# 01POWER.net
KiCad netlist of a schematic drawn in Altium Designer
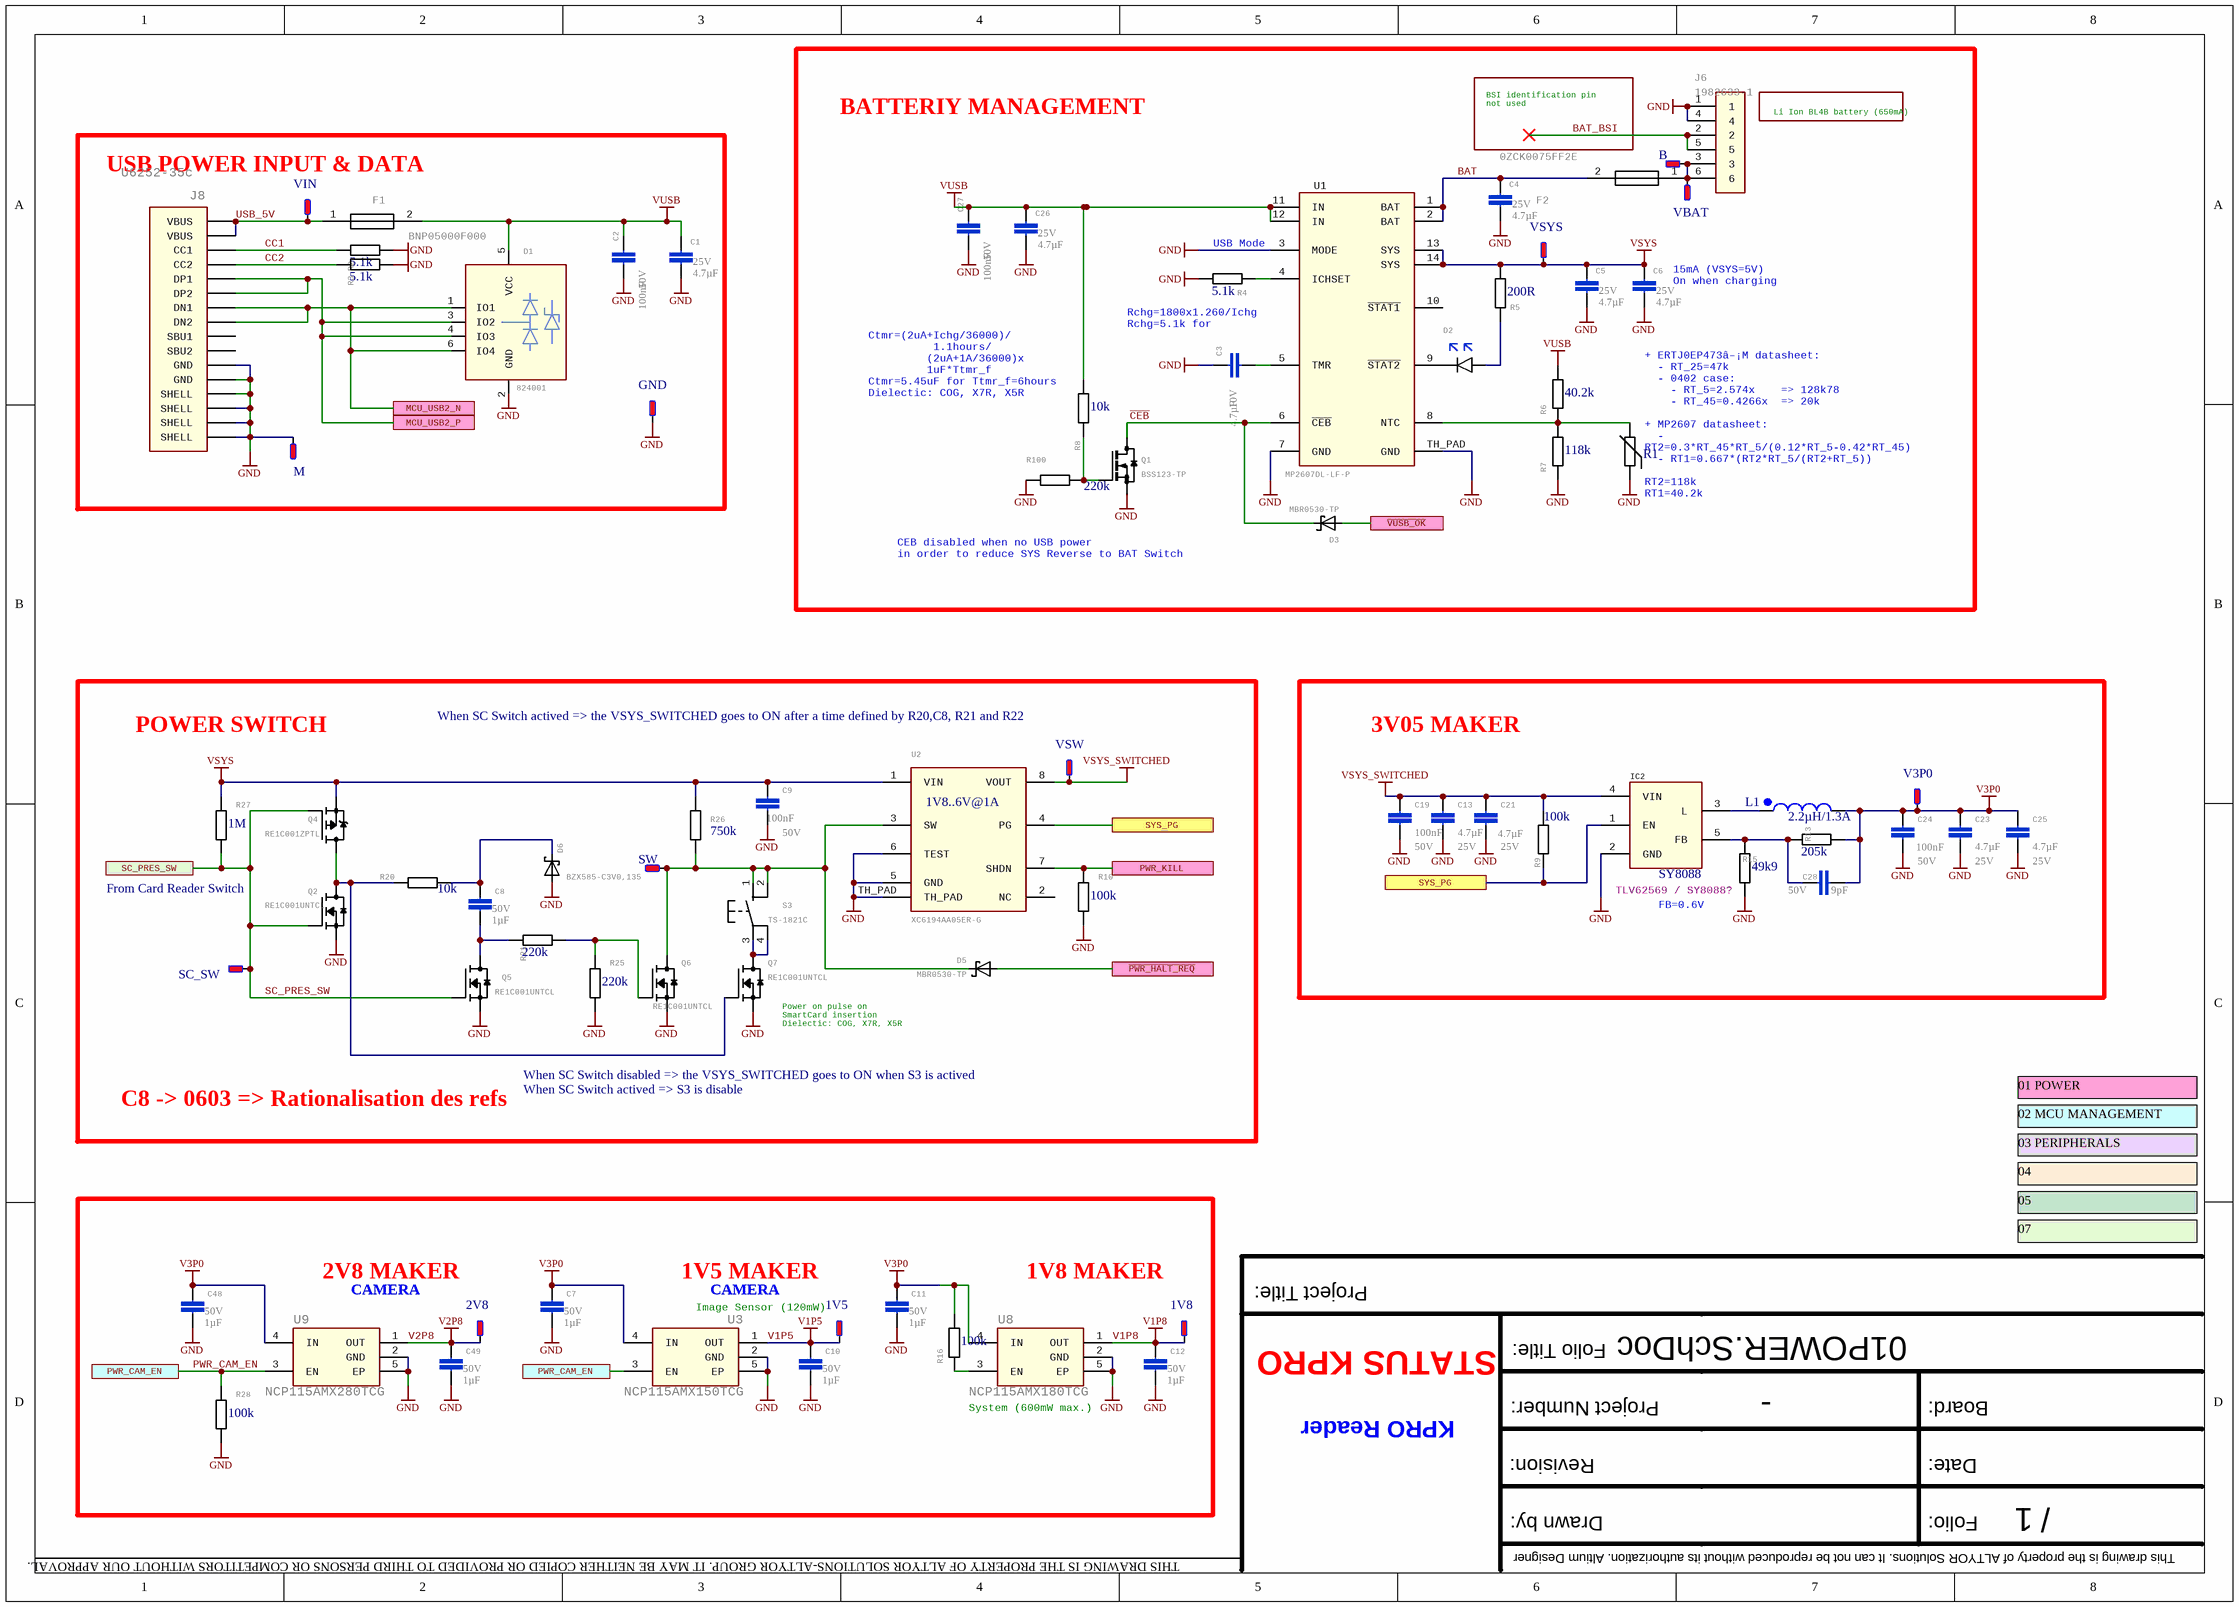
[diagram p0: 01POWER.SchDoc]

(export (version "E")
  (design (tool "Eeschema 10.0.6"))
  (components
    (comp (ref "1V5")
      (value "TP")
      (footprint "TESTPOINT 1MM")
      (description "Pointe de test 1.27mm")
      (libsource (lib "KCP-2282-600") (part "TP"))
    )
    (comp (ref "1V8")
      (value "TP")
      (footprint "TESTPOINT 1MM")
      (description "Pointe de test 1.27mm")
      (libsource (lib "KCP-2282-600") (part "TP"))
    )
    (comp (ref "2V8")
      (value "TP")
      (footprint "TESTPOINT 1MM")
      (description "Pointe de test 1.27mm")
      (libsource (lib "KCP-2282-600") (part "TP"))
    )
    (comp (ref "B")
      (value "TP")
      (footprint "PLAGE - ROUGE")
      (description "Pointe de test 1.27mm")
      (libsource (lib "KCP-2282-600") (part "TP"))
    )
    (comp (ref "C1")
      (value "0805X475M250CT")
      (footprint "0805 - CAPACITOR")
      (description "CAP X5R 4.7µF 25V ±10% 0805")
      (fields
        (field (name "MANUFACTURER") "WALSIN")
        (field (name "VOLTAGE") "25V")
        (field (name "NAME") "4.7µF")
      )
      (libsource (lib "KCP-2282-600") (part "C-EU-C4.7µF-X5R-6.3V-0805"))
    )
    (comp (ref "C2")
      (value "0402B104K500CT")
      (footprint "0402 - CAPACITOR")
      (description "CAP X7R 100nF 50V ±10% 0402")
      (fields
        (field (name "MANUFACTURER") "WALSIN")
        (field (name "VOLTAGE") "50V")
        (field (name "NAME") "100nF")
      )
      (libsource (lib "KCP-2282-600") (part "C-EU-C100NF-X7R-16V-0402"))
    )
    (comp (ref "C3")
      (value "CC0402KRX5R6BB475")
      (footprint "0402 - CAPACITOR")
      (description "CAP X5R 4.7µF 10V ±10% 0402")
      (fields
        (field (name "MANUFACTURER") "YAGEO")
        (field (name "VOLTAGE") "10V")
        (field (name "NAME") "4.7µF")
      )
      (libsource (lib "KCP-2282-600") (part "C-EU-C5UF-X7R-6.3V-0402"))
    )
    (comp (ref "C4")
      (value "0805X475M250CT")
      (footprint "0805 - CAPACITOR")
      (description "CAP X5R 4.7µF 25V ±10% 0805")
      (fields
        (field (name "MANUFACTURER") "WALSIN")
        (field (name "VOLTAGE") "25V")
        (field (name "NAME") "4.7µF")
      )
      (libsource (lib "KCP-2282-600") (part "C-EU-C4.7µF-X5R-6.3V-0805"))
    )
    (comp (ref "C5")
      (value "0805X475M250CT")
      (footprint "0805 - CAPACITOR")
      (description "CAP X5R 4.7µF 25V ±10% 0805")
      (fields
        (field (name "MANUFACTURER") "WALSIN")
        (field (name "VOLTAGE") "25V")
        (field (name "NAME") "4.7µF")
      )
      (libsource (lib "KCP-2282-600") (part "C-EU-C4.7µF-X5R-6.3V-0805"))
    )
    (comp (ref "C6")
      (value "0805X475M250CT")
      (footprint "0805 - CAPACITOR")
      (description "CAP X5R 4.7µF 25V ±10% 0805")
      (fields
        (field (name "MANUFACTURER") "WALSIN")
        (field (name "VOLTAGE") "25V")
        (field (name "NAME") "4.7µF")
      )
      (libsource (lib "KCP-2282-600") (part "C-EU-C4.7µF-X5R-6.3V-0805"))
    )
    (comp (ref "C7")
      (value "0603X105K500CT")
      (footprint "0603 - CAPACITOR")
      (description "CAP X5R 1µF 50V ±10% 0603")
      (fields
        (field (name "MANUFACTURER") "WALSIN")
        (field (name "VOLTAGE") "50V")
        (field (name "NAME") "1µF")
      )
      (libsource (lib "KCP-2282-600") (part "C-EU-C1µF-X5R-6.3V-0603"))
    )
    (comp (ref "C8")
      (value "0603X105K500CT")
      (footprint "0603 - CAPACITOR")
      (description "CAP X5R 1µF 50V ±10% 0603")
      (fields
        (field (name "MANUFACTURER") "WALSIN")
        (field (name "VOLTAGE") "50V")
        (field (name "NAME") "1µF")
      )
      (libsource (lib "KCP-2282-600") (part "C-EU-C1µF-X5R-6.3V-0603"))
    )
    (comp (ref "C9")
      (value "0402B104K500CT")
      (footprint "0402 - CAPACITOR")
      (description "CAP X7R 100nF 50V ±10% 0402")
      (fields
        (field (name "MANUFACTURER") "WALSIN")
        (field (name "VOLTAGE") "50V")
        (field (name "NAME") "100nF")
      )
      (libsource (lib "KCP-2282-600") (part "C-EU-C100NF-X7R-16V-0402"))
    )
    (comp (ref "C10")
      (value "0603X105K500CT")
      (footprint "0603 - CAPACITOR")
      (description "CAP X5R 1µF 50V ±10% 0603")
      (fields
        (field (name "MANUFACTURER") "WALSIN")
        (field (name "VOLTAGE") "50V")
        (field (name "NAME") "1µF")
      )
      (libsource (lib "KCP-2282-600") (part "C-EU-C1µF-X5R-6.3V-0603"))
    )
    (comp (ref "C11")
      (value "0603X105K500CT")
      (footprint "0603 - CAPACITOR")
      (description "CAP X5R 1µF 50V ±10% 0603")
      (fields
        (field (name "MANUFACTURER") "WALSIN")
        (field (name "VOLTAGE") "50V")
        (field (name "NAME") "1µF")
      )
      (libsource (lib "KCP-2282-600") (part "C-EU-C1µF-X5R-6.3V-0603"))
    )
    (comp (ref "C12")
      (value "0603X105K500CT")
      (footprint "0603 - CAPACITOR")
      (description "CAP X5R 1µF 50V ±10% 0603")
      (fields
        (field (name "MANUFACTURER") "WALSIN")
        (field (name "VOLTAGE") "50V")
        (field (name "NAME") "1µF")
      )
      (libsource (lib "KCP-2282-600") (part "C-EU-C1µF-X5R-6.3V-0603"))
    )
    (comp (ref "C13")
      (value "0805X475M250CT")
      (footprint "0805 - CAPACITOR")
      (description "CAP X5R 4.7µF 25V ±10% 0805")
      (fields
        (field (name "MANUFACTURER") "WALSIN")
        (field (name "VOLTAGE") "25V")
        (field (name "NAME") "4.7µF")
      )
      (libsource (lib "KCP-2282-600") (part "C-EU-C4.7µF-X5R-6.3V-0805"))
    )
    (comp (ref "C19")
      (value "0402B104K500CT")
      (footprint "0402 - CAPACITOR")
      (description "CAP X7R 100nF 50V ±10% 0402")
      (fields
        (field (name "MANUFACTURER") "WALSIN")
        (field (name "VOLTAGE") "50V")
        (field (name "NAME") "100nF")
      )
      (libsource (lib "KCP-2282-600") (part "C-EU-C100NF-X7R-16V-0402"))
    )
    (comp (ref "C21")
      (value "0805X475M250CT")
      (footprint "0805 - CAPACITOR")
      (description "CAP X5R 4.7µF 25V ±10% 0805")
      (fields
        (field (name "MANUFACTURER") "WALSIN")
        (field (name "VOLTAGE") "25V")
        (field (name "NAME") "4.7µF")
      )
      (libsource (lib "KCP-2282-600") (part "C-EU-C4.7µF-X5R-6.3V-0805"))
    )
    (comp (ref "C23")
      (value "0805X475M250CT")
      (footprint "0805 - CAPACITOR")
      (description "CAP X5R 4.7µF 25V ±10% 0805")
      (fields
        (field (name "MANUFACTURER") "WALSIN")
        (field (name "VOLTAGE") "25V")
        (field (name "NAME") "4.7µF")
      )
      (libsource (lib "KCP-2282-600") (part "C-EU-C4.7µF-X5R-6.3V-0805"))
    )
    (comp (ref "C24")
      (value "0402B104K500CT")
      (footprint "0402 - CAPACITOR")
      (description "CAP X7R 100nF 50V ±10% 0402")
      (fields
        (field (name "MANUFACTURER") "WALSIN")
        (field (name "VOLTAGE") "50V")
        (field (name "NAME") "100nF")
      )
      (libsource (lib "KCP-2282-600") (part "C-EU-C100NF-X7R-16V-0402"))
    )
    (comp (ref "C25")
      (value "0805X475M250CT")
      (footprint "0805 - CAPACITOR")
      (description "CAP X5R 4.7µF 25V ±10% 0805")
      (fields
        (field (name "MANUFACTURER") "WALSIN")
        (field (name "VOLTAGE") "25V")
        (field (name "NAME") "4.7µF")
      )
      (libsource (lib "KCP-2282-600") (part "C-EU-C4.7µF-X5R-6.3V-0805"))
    )
    (comp (ref "C26")
      (value "0805X475M250CT")
      (footprint "0805 - CAPACITOR")
      (description "CAP X5R 4.7µF 25V ±10% 0805")
      (fields
        (field (name "MANUFACTURER") "WALSIN")
        (field (name "VOLTAGE") "25V")
        (field (name "NAME") "4.7µF")
      )
      (libsource (lib "KCP-2282-600") (part "C-EU-C4.7µF-X5R-6.3V-0805"))
    )
    (comp (ref "C27")
      (value "0402B104K500CT")
      (footprint "0402 - CAPACITOR")
      (description "CAP X7R 100nF 50V ±10% 0402")
      (fields
        (field (name "MANUFACTURER") "WALSIN")
        (field (name "VOLTAGE") "50V")
        (field (name "NAME") "100nF")
      )
      (libsource (lib "KCP-2282-600") (part "C-EU-C100NF-X7R-16V-0402"))
    )
    (comp (ref "C28")
      (value "0402N9R0B500CT")
      (footprint "0402 - CAPACITOR")
      (description "CAP COG 9pF 50V ±0.1pF 0402")
      (fields
        (field (name "MANUFACTURER") "WALSIN")
        (field (name "VOLTAGE") "50V")
        (field (name "NAME") "9pF")
      )
      (libsource (lib "KCP-2282-600") (part "C-EU-C9PF-C0G-50V-0402"))
    )
    (comp (ref "C48")
      (value "0603X105K500CT")
      (footprint "0603 - CAPACITOR")
      (description "CAP X5R 1µF 50V ±10% 0603")
      (fields
        (field (name "MANUFACTURER") "WALSIN")
        (field (name "VOLTAGE") "50V")
        (field (name "NAME") "1µF")
      )
      (libsource (lib "KCP-2282-600") (part "C-EU-C1µF-X5R-6.3V-0603"))
    )
    (comp (ref "C49")
      (value "0603X105K500CT")
      (footprint "0603 - CAPACITOR")
      (description "CAP X5R 1µF 50V ±10% 0603")
      (fields
        (field (name "MANUFACTURER") "WALSIN")
        (field (name "VOLTAGE") "50V")
        (field (name "NAME") "1µF")
      )
      (libsource (lib "KCP-2282-600") (part "C-EU-C1µF-X5R-6.3V-0603"))
    )
    (comp (ref "D1")
      (value "824001")
      (footprint "SOT23-6 0.95 Var AA")
      (description "diode TVS, 82400 Series, Bidirectionelle")
      (fields (field (name "MANUFACTURER") "Würth"))
      (libsource (lib "KCP-2282-600") (part "824001"))
    )
    (comp (ref "D2")
      (value "LR_Y8SF-U1V2-1")
      (footprint "OSRAM LRY8SFU1V21")
      (description "Osram Opto Micro SIDELED Series Red LED, 120    Source:  Datasheet")
      (fields (field (name "MANUFACTURER") "OSRAM"))
      (libsource (lib "KCP-2282-600") (part "LR_Y8SF-U1V2-1"))
    )
    (comp (ref "D3")
      (value "MBR0530-TP")
      (footprint "SOD123 DIODE INC")
      (description "Schottky Rectifier, 30 V, 500 mA, Single")
      (fields (field (name "MANUFACTURER") "ON SEMI"))
      (libsource (lib "KCP-2282-600") (part "MBR0530T1G"))
    )
    (comp (ref "D5")
      (value "MBR0530-TP")
      (footprint "SOD123 DIODE INC")
      (description "Schottky Rectifier, 30 V, 500 mA, Single")
      (fields (field (name "MANUFACTURER") "ON SEMI"))
      (libsource (lib "KCP-2282-600") (part "MBR0530T1G"))
    )
    (comp (ref "D6")
      (value "BZX585-C3V0,135")
      (footprint "SOD523 TOSHIBA")
      (description "Zener 3V, 300mW - SOD 523-3")
      (fields (field (name "MANUFACTURER") "NXP"))
      (libsource (lib "KCP-2282-600") (part "MBR0530T1G"))
    )
    (comp (ref "F1")
      (value "BNP05000F000")
      (footprint "0805 - FUSE")
      (description "FUSE 500mA 6V 0805")
      (fields (field (name "MANUFACTURER") "JNHONGBAO"))
      (libsource (lib "KCP-2282-600") (part "0ZCK0050FF2E"))
    )
    (comp (ref "F2")
      (value "0ZCK0075FF2E")
      (footprint "0805 - FUSE")
      (fields (field (name "MANUFACTURER") "Bel Circuit Protection"))
      (libsource (lib "KCP-2282-600") (part "0ZCK0075FF2E"))
    )
    (comp (ref "GND")
      (value "TP")
      (footprint "TESTPOINT 1MM")
      (description "Pointe de test 1.27mm")
      (libsource (lib "KCP-2282-600") (part "TP"))
    )
    (comp (ref "IC2")
      (value "SY8088IAAC")
      (footprint "SOT23-5 0.95 Var AA")
      (description "DCDC 2V5..5V5  50µA 1V8..3V3")
      (fields (field (name "MANUFACTURER") "SILERGY") (field (name "NAME") "SY8088"))
      (libsource (lib "KCP-2282-600") (part "SILERGY SI8088IAAC"))
    )
    (comp (ref "J6")
      (value "1982633-1")
      (footprint "TE 19826331")
      (description "Connecteurs carte Ã  carte et mezzanine BATTERY CONN 3 POSITION")
      (fields (field (name "MANUFACTURER") "TE Connectivity"))
      (libsource (lib "KCP-2282-600") (part "1982633-1"))
    )
    (comp (ref "J8")
      (value "U6252-35c")
      (footprint "ANTENK U6252-35C")
      (description "Connecteurs USB USB C Rec 16P 3u\" Mid Mnt 1.6mm O-set SMT L = 6.5mm S-Spring")
      (fields (field (name "MANUFACTURER") "ANTENK"))
      (libsource (lib "KCP-2282-600") (part "ANTENK U6252-35c"))
    )
    (comp (ref "L1")
      (value "BWVF002520122R2M00")
      (footprint "CHILISON BWF00252012")
      (description "IND 2.2µH, 20%, 1.8A 68mOhm 1MHz - 2.5x2")
      (fields (field (name "MANUFACTURER") "CHILISIN") (field (name "NAME") "2.2µH/1.3A"))
      (libsource (lib "KCP-2282-600") (part "CDRH5D28NP-100NC"))
    )
    (comp (ref "M")
      (value "TP")
      (footprint "PLAGE - NOIRE")
      (description "Pointe de test 1.27mm")
      (libsource (lib "KCP-2282-600") (part "TP"))
    )
    (comp (ref "Q1")
      (value "BSS123-TP")
      (footprint "SOT23-VAR AB")
      (description "MOS N 100V 170mA Rds6R - SOT23")
      (fields (field (name "MANUFACTURER") "MCC"))
      (libsource (lib "KCP-2282-600") (part "BSS123"))
    )
    (comp (ref "Q2")
      (value "RE1C001UNTCL")
      (footprint "SOT-416-3")
      (description "MOS N 20V 100mA Rds3.5R")
      (fields (field (name "MANUFACTURER") "ROHM SEMI"))
      (libsource (lib "KCP-2282-600") (part "RE1C001UNTCL"))
    )
    (comp (ref "Q4")
      (value "RE1C001ZPTL")
      (footprint "SOT-416-3")
      (description "MOS P 20V 100mA Rds3.8R")
      (fields (field (name "MANUFACTURER") "ROHM SEMI"))
      (libsource (lib "KCP-2282-600") (part "RE1C001ZPTL"))
    )
    (comp (ref "Q5")
      (value "RE1C001UNTCL")
      (footprint "SOT-416-3")
      (description "MOS N 20V 100mA Rds3.5R")
      (fields (field (name "MANUFACTURER") "ROHM SEMI"))
      (libsource (lib "KCP-2282-600") (part "RE1C001UNTCL"))
    )
    (comp (ref "Q6")
      (value "RE1C001UNTCL")
      (footprint "SOT-416-3")
      (description "MOS N 20V 100mA Rds3.5R")
      (fields (field (name "MANUFACTURER") "ROHM SEMI"))
      (libsource (lib "KCP-2282-600") (part "RE1C001UNTCL"))
    )
    (comp (ref "Q7")
      (value "RE1C001UNTCL")
      (footprint "SOT-416-3")
      (description "MOS N 20V 100mA Rds3.5R")
      (fields (field (name "MANUFACTURER") "ROHM SEMI"))
      (libsource (lib "KCP-2282-600") (part "RE1C001UNTCL"))
    )
    (comp (ref "R1")
      (value "ERT-J0EP473GM")
      (footprint "0402 - RESISTOR")
      (description "CTN 47k 2% B(25/50) 4050K 0/+1% - 0402")
      (fields (field (name "MANUFACTURER") "PANASONIC"))
      (libsource (lib "KCP-2282-600") (part "ERT-J0EP473GM"))
    )
    (comp (ref "R2")
      (value "RC0402FR-075K1L")
      (footprint "0402 - RESISTOR")
      (description "RES 5.1k 63mW 1% 0402")
      (fields (field (name "MANUFACTURER") "YAGEO") (field (name "NAME") "5.1k"))
      (libsource (lib "KCP-2282-600") (part "R-EU-R5.1K-1%-0402"))
    )
    (comp (ref "R3")
      (value "RC0402FR-075K1L")
      (footprint "0402 - RESISTOR")
      (description "RES 5.1k 63mW 1% 0402")
      (fields (field (name "MANUFACTURER") "YAGEO") (field (name "NAME") "5.1k"))
      (libsource (lib "KCP-2282-600") (part "R-EU-R5.1K-1%-0402"))
    )
    (comp (ref "R4")
      (value "RC0402FR-075K1L")
      (footprint "0402 - RESISTOR")
      (description "RES 5.1k 63mW 1% 0402")
      (fields (field (name "MANUFACTURER") "YAGEO") (field (name "NAME") "5.1k"))
      (libsource (lib "KCP-2282-600") (part "R-EU-R4.53K-1%-0402"))
    )
    (comp (ref "R5")
      (value "RC0402FR-07200RL")
      (footprint "0402 - RESISTOR")
      (description "RES 200R 63mW 1% 0402")
      (fields (field (name "MANUFACTURER") "YAGEO") (field (name "NAME") "200R"))
      (libsource (lib "KCP-2282-600") (part "R-EU-R200-1%-0402"))
    )
    (comp (ref "R6")
      (value "RC0402FR-0740K2L")
      (footprint "0402 - RESISTOR")
      (description "RES 40.2k 63mW 1% 0402")
      (fields (field (name "MANUFACTURER") "YAGEO") (field (name "NAME") "40.2k"))
      (libsource (lib "KCP-2282-600") (part "R-EU-R40.2K-1%-0402"))
    )
    (comp (ref "R7")
      (value "RC0402FR-07118KL")
      (footprint "0402 - RESISTOR")
      (description "RES 118k 63mW 1% 0402")
      (fields (field (name "MANUFACTURER") "YAGEO") (field (name "NAME") "118k"))
      (libsource (lib "KCP-2282-600") (part "R-EU-R118K-1%-0402"))
    )
    (comp (ref "R8")
      (value "RC0402FR-0710KL")
      (footprint "0402 - RESISTOR")
      (description "RES 10k 63mW 1% 0402")
      (fields (field (name "MANUFACTURER") "YAGEO") (field (name "NAME") "10k"))
      (libsource (lib "KCP-2282-600") (part "R-EU-R10K-1%-0402"))
    )
    (comp (ref "R9")
      (value "RC0402FR-07100KL")
      (footprint "0402 - RESISTOR")
      (description "RES 100k 63mW 1% 0402")
      (fields (field (name "MANUFACTURER") "YAGEO") (field (name "NAME") "100k"))
      (libsource (lib "KCP-2282-600") (part "R-EU-R100K-1%-0402"))
    )
    (comp (ref "R10")
      (value "RC0402FR-07100KL")
      (footprint "0402 - RESISTOR")
      (description "RES 100k 63mW 1% 0402")
      (fields (field (name "MANUFACTURER") "YAGEO") (field (name "NAME") "100k"))
      (libsource (lib "KCP-2282-600") (part "R-EU-R100K-1%-0402"))
    )
    (comp (ref "R13")
      (value "RC0402FR-07205KL")
      (footprint "0402 - RESISTOR")
      (description "RES 205k 63mW 1% 0402")
      (fields (field (name "MANUFACTURER") "YAGEO") (field (name "NAME") "205k"))
      (libsource (lib "KCP-2282-600") (part "R-EU-R100K-1%-0402"))
    )
    (comp (ref "R15")
      (value "RC0402FR-0749K9L")
      (footprint "0402 - RESISTOR")
      (description "RES 49k9 63mW 1% 0402")
      (fields (field (name "MANUFACTURER") "YAGEO") (field (name "NAME") "49k9"))
      (libsource (lib "KCP-2282-600") (part "R-EU-R100K-1%-0402"))
    )
    (comp (ref "R16")
      (value "RC0402FR-07100KL")
      (footprint "0402 - RESISTOR")
      (description "RES 100k 63mW 1% 0402")
      (fields (field (name "MANUFACTURER") "YAGEO") (field (name "NAME") "100k"))
      (libsource (lib "KCP-2282-600") (part "R-EU-R100K-1%-0402"))
    )
    (comp (ref "R20")
      (value "RC0402FR-0710KL")
      (footprint "0402 - RESISTOR")
      (description "RES 10k 63mW 1% 0402")
      (fields (field (name "MANUFACTURER") "YAGEO") (field (name "NAME") "10k"))
      (libsource (lib "KCP-2282-600") (part "R-EU-R10K-1%-0402"))
    )
    (comp (ref "R21")
      (value "RC0402FR-07220KL")
      (footprint "0402 - RESISTOR")
      (description "RES 220k 63mW 1% 0402")
      (fields (field (name "MANUFACTURER") "YAGEO") (field (name "NAME") "220k"))
      (libsource (lib "KCP-2282-600") (part "R-EU-R220K-1%-0402"))
    )
    (comp (ref "R25")
      (value "RC0402FR-07220KL")
      (footprint "0402 - RESISTOR")
      (description "RES 220k 63mW 1% 0402")
      (fields (field (name "MANUFACTURER") "YAGEO") (field (name "NAME") "220k"))
      (libsource (lib "KCP-2282-600") (part "R-EU-R220K-1%-0402"))
    )
    (comp (ref "R26")
      (value "RC0402FR-07750KL")
      (footprint "0402 - RESISTOR")
      (description "RES 750k 63mW 1% 0402")
      (fields (field (name "MANUFACTURER") "YAGEO") (field (name "NAME") "750k"))
      (libsource (lib "KCP-2282-600") (part "R-EU-R750K-1%-0402"))
    )
    (comp (ref "R27")
      (value "RC0201FR-071ML")
      (footprint "0402 - RESISTOR")
      (description "RES 1M 63mW 1% 0402")
      (fields (field (name "MANUFACTURER") "YAGEO") (field (name "NAME") "1M"))
      (libsource (lib "KCP-2282-600") (part "R-EU-R1M-1%-0402"))
    )
    (comp (ref "R28")
      (value "RC0402FR-07100KL")
      (footprint "0402 - RESISTOR")
      (description "RES 100k 63mW 1% 0402")
      (fields (field (name "MANUFACTURER") "YAGEO") (field (name "NAME") "100k"))
      (libsource (lib "KCP-2282-600") (part "R-EU-R100K-1%-0402"))
    )
    (comp (ref "R100")
      (value "RC0402FR-07220KL")
      (footprint "0402 - RESISTOR")
      (description "RES 220k 63mW 1% 0402")
      (fields (field (name "MANUFACTURER") "YAGEO") (field (name "NAME") "220k"))
      (libsource (lib "KCP-2282-600") (part "R-EU-R220K-1%-0402"))
    )
    (comp (ref "S3")
      (value "TS-1821C")
      (footprint "SONG TS1821C")
      (description "Interrupteurs de contact WS-TASU SMD Switch 3.5x2.9 x1.35mm")
      (fields (field (name "MANUFACTURER") "SONG"))
      (libsource (lib "KCP-2282-600") (part "434331013822"))
    )
    (comp (ref "SC_SW")
      (value "TP")
      (footprint "TESTPOINT 1MM")
      (description "Pointe de test 1.27mm")
      (libsource (lib "KCP-2282-600") (part "TP"))
    )
    (comp (ref "SW")
      (value "TP")
      (footprint "TESTPOINT 1MM")
      (description "Pointe de test 1.27mm")
      (libsource (lib "KCP-2282-600") (part "TP"))
    )
    (comp (ref "U1")
      (value "MP2607DL-LF-P")
      (footprint "QFN14-0.5-3s4")
      (description "Li + LINEAR Charger WithSystem Power Path Management")
      (fields (field (name "MANUFACTURER") "MPS"))
      (libsource (lib "KCP-2282-600") (part "MP2607DL-LF-P"))
    )
    (comp (ref "U2")
      (value "XC6194AA05ER-G")
      (footprint "TOREX USP-8B06")
      (description "Power saving Push Button Load switch")
      (fields (field (name "MANUFACTURER") "TOREX"))
      (libsource (lib "KCP-2282-600") (part "XC6194AA05ER-G"))
    )
    (comp (ref "U3")
      (value "NCP115AMX150TCG")
      (footprint "ON SEMI NCV8160AMX330TBG")
      (description "LDO Regulator - High PSRR - 300mA - Input Voltage 1.7V/5.5V - Ouput Voltage 1.5V")
      (fields (field (name "MANUFACTURER") "ON SEMI"))
      (libsource (lib "KCP-2282-600") (part "NCP115AMX150TCG"))
    )
    (comp (ref "U8")
      (value "NCP115AMX180TCG")
      (footprint "ON SEMI NCV8160AMX330TBG")
      (description "LDO Regulator - High PSRR - 300mA - Input Voltage 1.7V/5.5V - Ouput Voltage 1.8V")
      (fields (field (name "MANUFACTURER") "ON SEMI"))
      (libsource (lib "KCP-2282-600") (part "NCP115AMX180TCG"))
    )
    (comp (ref "U9")
      (value "NCP115AMX280TCG")
      (footprint "ON SEMI NCV8160AMX330TBG")
      (description "LDO Regulator - High PSRR - 300mA - Input Voltage 1.7V/5.5V - Ouput Voltage 2.8V")
      (fields (field (name "MANUFACTURER") "ON SEMI"))
      (libsource (lib "KCP-2282-600") (part "NCP115AMX280TCG"))
    )
    (comp (ref "V3P0")
      (value "TP")
      (footprint "TESTPOINT 1MM")
      (description "Pointe de test 1.27mm")
      (libsource (lib "KCP-2282-600") (part "TP"))
    )
    (comp (ref "VBAT")
      (value "TP")
      (footprint "TESTPOINT 1MM")
      (description "Pointe de test 1.27mm")
      (libsource (lib "KCP-2282-600") (part "TP"))
    )
    (comp (ref "VIN")
      (value "TP")
      (footprint "TESTPOINT 1MM")
      (description "Pointe de test 1.27mm")
      (libsource (lib "KCP-2282-600") (part "TP"))
    )
    (comp (ref "VSW")
      (value "TP")
      (footprint "TESTPOINT 1MM")
      (description "Pointe de test 1.27mm")
      (libsource (lib "KCP-2282-600") (part "TP"))
    )
    (comp (ref "VSYS")
      (value "TP")
      (footprint "TESTPOINT 1MM")
      (description "Pointe de test 1.27mm")
      (libsource (lib "KCP-2282-600") (part "TP"))
    )
  )
  (nets
    (net (code "1") (name "/BAT") (class "Default")
      (node (ref "C4") (pin "1") (pinfunction "1_1") (pintype "passive"))
      (node (ref "F2") (pin "2") (pinfunction "2_2") (pintype "passive"))
      (node (ref "U1") (pin "1") (pinfunction "BAT_1") (pintype "passive"))
      (node (ref "U1") (pin "2") (pinfunction "BAT_2") (pintype "passive"))
    )
    (net (code "2") (name "/BAT_BSI") (class "Default")
      (node (ref "J6") (pin "2") (pinfunction "2_2") (pintype "passive"))
      (node (ref "J6") (pin "5") (pinfunction "5_5") (pintype "passive"))
    )
    (net (code "3") (name "/CC1") (class "Default")
      (node (ref "J8") (pin "A5") (pinfunction "CC1_A5") (pintype "passive"))
      (node (ref "R2") (pin "2") (pinfunction "2_2") (pintype "passive"))
    )
    (net (code "4") (name "/CC2") (class "Default")
      (node (ref "J8") (pin "B5") (pinfunction "CC2_B5") (pintype "passive"))
      (node (ref "R3") (pin "2") (pinfunction "2_2") (pintype "passive"))
    )
    (net (code "5") (name "/MCU_USB2_N") (class "Default")
      (node (ref "D1") (pin "1") (pinfunction "IO1_1") (pintype "passive"))
      (node (ref "D1") (pin "6") (pinfunction "IO4_6") (pintype "passive"))
      (node (ref "J8") (pin "A7") (pinfunction "DN1_A7") (pintype "passive"))
      (node (ref "J8") (pin "B7") (pinfunction "DN2_B7") (pintype "passive"))
    )
    (net (code "6") (name "/MCU_USB2_P") (class "Default")
      (node (ref "D1") (pin "3") (pinfunction "IO2_3") (pintype "passive"))
      (node (ref "D1") (pin "4") (pinfunction "IO3_4") (pintype "passive"))
      (node (ref "J8") (pin "A6") (pinfunction "DP1_A6") (pintype "passive"))
      (node (ref "J8") (pin "B6") (pinfunction "DP2_B6") (pintype "passive"))
    )
    (net (code "7") (name "/PWR_CAM_EN") (class "Default")
      (node (ref "R28") (pin "2") (pinfunction "2_2") (pintype "passive"))
      (node (ref "U3") (pin "3") (pinfunction "EN_3") (pintype "passive"))
      (node (ref "U9") (pin "3") (pinfunction "EN_3") (pintype "passive"))
    )
    (net (code "8") (name "/PWR_KILL") (class "Default")
      (node (ref "R10") (pin "2") (pinfunction "2_2") (pintype "passive"))
      (node (ref "U2") (pin "7") (pinfunction "SHDN_7") (pintype "passive"))
    )
    (net (code "9") (name "/SC_PRES_SW") (class "Default")
      (node (ref "Q2") (pin "1") (pinfunction "G_1") (pintype "passive"))
      (node (ref "Q4") (pin "1") (pinfunction "G_1") (pintype "passive"))
      (node (ref "Q5") (pin "1") (pinfunction "G_1") (pintype "passive"))
      (node (ref "R27") (pin "1") (pinfunction "1_1") (pintype "passive"))
      (node (ref "SC_SW") (pin "1") (pinfunction "PT_1") (pintype "passive"))
    )
    (net (code "10") (name "/SYS_PG") (class "Default")
      (node (ref "IC2") (pin "1") (pinfunction "EN_1") (pintype "passive"))
      (node (ref "R9") (pin "2") (pinfunction "2_2") (pintype "passive"))
      (node (ref "U2") (pin "4") (pinfunction "PG_4") (pintype "passive"))
    )
    (net (code "11") (name "/USB_5V") (class "Default")
      (node (ref "F1") (pin "1") (pinfunction "1_1") (pintype "passive"))
      (node (ref "J8") (pin "A4_B9") (pinfunction "VBUS_A4_B9") (pintype "passive"))
      (node (ref "J8") (pin "B4_A9") (pinfunction "VBUS_B4_A9") (pintype "passive"))
      (node (ref "VIN") (pin "1") (pinfunction "PT_1") (pintype "passive"))
    )
    (net (code "12") (name "/~{CEB}") (class "Default")
      (node (ref "D3") (pin "C") (pinfunction "C_C") (pintype "passive"))
      (node (ref "Q1") (pin "3") (pinfunction "D_3") (pintype "passive"))
      (node (ref "U1") (pin "6") (pinfunction "~{CEB}_6") (pintype "passive"))
    )
    (net (code "13") (name "/~{PWR_HALT_REQ}") (class "Default")
      (node (ref "D5") (pin "A") (pinfunction "A_A") (pintype "passive"))
    )
    (net (code "14") (name "/~{VUSB_OK}") (class "Default")
      (node (ref "D3") (pin "A") (pinfunction "A_A") (pintype "passive"))
    )
    (net (code "15") (name "GND") (class "Default")
      (node (ref "C1") (pin "2") (pinfunction "2_2") (pintype "passive"))
      (node (ref "C10") (pin "2") (pinfunction "2_2") (pintype "passive"))
      (node (ref "C11") (pin "2") (pinfunction "2_2") (pintype "passive"))
      (node (ref "C12") (pin "2") (pinfunction "2_2") (pintype "passive"))
      (node (ref "C13") (pin "2") (pinfunction "2_2") (pintype "passive"))
      (node (ref "C19") (pin "2") (pinfunction "2_2") (pintype "passive"))
      (node (ref "C2") (pin "2") (pinfunction "2_2") (pintype "passive"))
      (node (ref "C21") (pin "2") (pinfunction "2_2") (pintype "passive"))
      (node (ref "C23") (pin "2") (pinfunction "2_2") (pintype "passive"))
      (node (ref "C24") (pin "2") (pinfunction "2_2") (pintype "passive"))
      (node (ref "C25") (pin "2") (pinfunction "2_2") (pintype "passive"))
      (node (ref "C26") (pin "2") (pinfunction "2_2") (pintype "passive"))
      (node (ref "C27") (pin "2") (pinfunction "2_2") (pintype "passive"))
      (node (ref "C3") (pin "1") (pinfunction "1_1") (pintype "passive"))
      (node (ref "C4") (pin "2") (pinfunction "2_2") (pintype "passive"))
      (node (ref "C48") (pin "2") (pinfunction "2_2") (pintype "passive"))
      (node (ref "C49") (pin "2") (pinfunction "2_2") (pintype "passive"))
      (node (ref "C5") (pin "2") (pinfunction "2_2") (pintype "passive"))
      (node (ref "C6") (pin "2") (pinfunction "2_2") (pintype "passive"))
      (node (ref "C7") (pin "2") (pinfunction "2_2") (pintype "passive"))
      (node (ref "C9") (pin "2") (pinfunction "2_2") (pintype "passive"))
      (node (ref "D1") (pin "2") (pinfunction "GND_2") (pintype "passive"))
      (node (ref "D6") (pin "A") (pinfunction "A_A") (pintype "passive"))
      (node (ref "GND") (pin "1") (pinfunction "PT_1") (pintype "passive"))
      (node (ref "IC2") (pin "2") (pinfunction "GND_2") (pintype "passive"))
      (node (ref "J6") (pin "1") (pinfunction "1_1") (pintype "passive"))
      (node (ref "J6") (pin "4") (pinfunction "4_4") (pintype "passive"))
      (node (ref "J8") (pin "A1_B12") (pinfunction "GND_A1_B12") (pintype "passive"))
      (node (ref "J8") (pin "B1_A12") (pinfunction "GND_B1_A12") (pintype "passive"))
      (node (ref "J8") (pin "S1") (pinfunction "SHELL_S1") (pintype "passive"))
      (node (ref "J8") (pin "S2") (pinfunction "SHELL_S2") (pintype "passive"))
      (node (ref "J8") (pin "S3") (pinfunction "SHELL_S3") (pintype "passive"))
      (node (ref "J8") (pin "S4") (pinfunction "SHELL_S4") (pintype "passive"))
      (node (ref "M") (pin "1") (pinfunction "PT_1") (pintype "passive"))
      (node (ref "Q1") (pin "2") (pinfunction "S_2") (pintype "passive"))
      (node (ref "Q2") (pin "2") (pinfunction "S_2") (pintype "passive"))
      (node (ref "Q5") (pin "2") (pinfunction "S_2") (pintype "passive"))
      (node (ref "Q6") (pin "2") (pinfunction "S_2") (pintype "passive"))
      (node (ref "Q7") (pin "2") (pinfunction "S_2") (pintype "passive"))
      (node (ref "R1") (pin "1") (pinfunction "1_1") (pintype "passive"))
      (node (ref "R10") (pin "1") (pinfunction "1_1") (pintype "passive"))
      (node (ref "R100") (pin "1") (pinfunction "1_1") (pintype "passive"))
      (node (ref "R15") (pin "1") (pinfunction "1_1") (pintype "passive"))
      (node (ref "R2") (pin "1") (pinfunction "1_1") (pintype "passive"))
      (node (ref "R25") (pin "1") (pinfunction "1_1") (pintype "passive"))
      (node (ref "R28") (pin "1") (pinfunction "1_1") (pintype "passive"))
      (node (ref "R3") (pin "1") (pinfunction "1_1") (pintype "passive"))
      (node (ref "R4") (pin "2") (pinfunction "2_2") (pintype "passive"))
      (node (ref "R7") (pin "1") (pinfunction "1_1") (pintype "passive"))
      (node (ref "U1") (pin "3") (pinfunction "MODE_3") (pintype "passive"))
      (node (ref "U1") (pin "7") (pinfunction "GND_7") (pintype "passive"))
      (node (ref "U1") (pin "TH_PAD") (pinfunction "GND_TH_PAD") (pintype "passive"))
      (node (ref "U2") (pin "5") (pinfunction "GND_5") (pintype "passive"))
      (node (ref "U2") (pin "6") (pinfunction "TEST_6") (pintype "passive"))
      (node (ref "U2") (pin "TH_PAD") (pinfunction "TH_PAD_TH_PAD") (pintype "passive"))
      (node (ref "U3") (pin "2") (pinfunction "GND_2") (pintype "passive"))
      (node (ref "U3") (pin "5") (pinfunction "EP_5") (pintype "passive"))
      (node (ref "U8") (pin "2") (pinfunction "GND_2") (pintype "passive"))
      (node (ref "U8") (pin "5") (pinfunction "EP_5") (pintype "passive"))
      (node (ref "U9") (pin "2") (pinfunction "GND_2") (pintype "passive"))
      (node (ref "U9") (pin "5") (pinfunction "EP_5") (pintype "passive"))
    )
    (net (code "16") (name "Net-(B-PT)") (class "Default")
      (node (ref "B") (pin "1") (pinfunction "PT_1") (pintype "passive"))
      (node (ref "F2") (pin "1") (pinfunction "1_1") (pintype "passive"))
      (node (ref "J6") (pin "3") (pinfunction "3_3") (pintype "passive"))
      (node (ref "J6") (pin "6") (pinfunction "6_6") (pintype "passive"))
      (node (ref "VBAT") (pin "1") (pinfunction "PT_1") (pintype "passive"))
    )
    (net (code "17") (name "Net-(C8-Pad1)") (class "Default")
      (node (ref "C8") (pin "1") (pinfunction "1_1") (pintype "passive"))
      (node (ref "D6") (pin "C") (pinfunction "C_C") (pintype "passive"))
      (node (ref "R20") (pin "2") (pinfunction "2_2") (pintype "passive"))
    )
    (net (code "18") (name "Net-(D2-A)") (class "Default")
      (node (ref "D2") (pin "2") (pinfunction "A_2") (pintype "passive"))
      (node (ref "R5") (pin "2") (pinfunction "2_2") (pintype "passive"))
    )
    (net (code "19") (name "Net-(D2-C)") (class "Default")
      (node (ref "D2") (pin "1") (pinfunction "C_1") (pintype "passive"))
      (node (ref "U1") (pin "9") (pinfunction "~{STAT2}_9") (pintype "passive"))
    )
    (net (code "20") (name "Net-(IC2-FB)") (class "Default")
      (node (ref "C28") (pin "1") (pinfunction "1_1") (pintype "passive"))
      (node (ref "IC2") (pin "5") (pinfunction "FB_5") (pintype "passive"))
      (node (ref "R13") (pin "2") (pinfunction "2_2") (pintype "passive"))
      (node (ref "R15") (pin "2") (pinfunction "2_2") (pintype "passive"))
    )
    (net (code "21") (name "Net-(IC2-L)") (class "Default")
      (node (ref "IC2") (pin "3") (pinfunction "L_3") (pintype "passive"))
      (node (ref "L1") (pin "1") (pinfunction "1_1") (pintype "passive"))
    )
    (net (code "22") (name "Net-(Q1-G)") (class "Default")
      (node (ref "Q1") (pin "1") (pinfunction "G_1") (pintype "passive"))
      (node (ref "R100") (pin "2") (pinfunction "2_2") (pintype "passive"))
      (node (ref "R8") (pin "1") (pinfunction "1_1") (pintype "passive"))
    )
    (net (code "23") (name "Net-(Q2-D)") (class "Default")
      (node (ref "Q2") (pin "3") (pinfunction "D_3") (pintype "passive"))
      (node (ref "Q4") (pin "3") (pinfunction "D_3") (pintype "passive"))
      (node (ref "Q7") (pin "1") (pinfunction "G_1") (pintype "passive"))
      (node (ref "R20") (pin "1") (pinfunction "1_1") (pintype "passive"))
    )
    (net (code "24") (name "Net-(Q5-D)") (class "Default")
      (node (ref "C8") (pin "2") (pinfunction "2_2") (pintype "passive"))
      (node (ref "Q5") (pin "3") (pinfunction "D_3") (pintype "passive"))
      (node (ref "R21") (pin "2") (pinfunction "2_2") (pintype "passive"))
    )
    (net (code "25") (name "Net-(Q6-D)") (class "Default")
      (node (ref "D5") (pin "C") (pinfunction "C_C") (pintype "passive"))
      (node (ref "Q6") (pin "3") (pinfunction "D_3") (pintype "passive"))
      (node (ref "R26") (pin "1") (pinfunction "1_1") (pintype "passive"))
      (node (ref "S3") (pin "1") (pinfunction "S_1") (pintype "passive"))
      (node (ref "S3") (pin "2") (pinfunction "S1_2") (pintype "passive"))
      (node (ref "SW") (pin "1") (pinfunction "PT_1") (pintype "passive"))
      (node (ref "U2") (pin "3") (pinfunction "SW_3") (pintype "passive"))
    )
    (net (code "26") (name "Net-(Q6-G)") (class "Default")
      (node (ref "Q6") (pin "1") (pinfunction "G_1") (pintype "passive"))
      (node (ref "R21") (pin "1") (pinfunction "1_1") (pintype "passive"))
      (node (ref "R25") (pin "2") (pinfunction "2_2") (pintype "passive"))
    )
    (net (code "27") (name "Net-(Q7-D)") (class "Default")
      (node (ref "Q7") (pin "3") (pinfunction "D_3") (pintype "passive"))
      (node (ref "S3") (pin "3") (pinfunction "P_3") (pintype "passive"))
      (node (ref "S3") (pin "4") (pinfunction "P1_4") (pintype "passive"))
    )
    (net (code "28") (name "Net-(U1-ICHSET)") (class "Default")
      (node (ref "R4") (pin "1") (pinfunction "1_1") (pintype "passive"))
      (node (ref "U1") (pin "4") (pinfunction "ICHSET_4") (pintype "passive"))
    )
    (net (code "29") (name "Net-(U1-NTC)") (class "Default")
      (node (ref "R1") (pin "2") (pinfunction "2_2") (pintype "passive"))
      (node (ref "R6") (pin "1") (pinfunction "1_1") (pintype "passive"))
      (node (ref "R7") (pin "2") (pinfunction "2_2") (pintype "passive"))
      (node (ref "U1") (pin "8") (pinfunction "NTC_8") (pintype "passive"))
    )
    (net (code "30") (name "Net-(U1-TMR)") (class "Default")
      (node (ref "C3") (pin "2") (pinfunction "2_2") (pintype "passive"))
      (node (ref "U1") (pin "5") (pinfunction "TMR_5") (pintype "passive"))
    )
    (net (code "31") (name "Net-(U8-EN)") (class "Default")
      (node (ref "R16") (pin "2") (pinfunction "2_2") (pintype "passive"))
      (node (ref "U8") (pin "3") (pinfunction "EN_3") (pintype "passive"))
    )
    (net (code "32") (name "V1P5") (class "Default")
      (node (ref "1V5") (pin "1") (pinfunction "PT_1") (pintype "passive"))
      (node (ref "C10") (pin "1") (pinfunction "1_1") (pintype "passive"))
      (node (ref "U3") (pin "1") (pinfunction "OUT_1") (pintype "passive"))
    )
    (net (code "33") (name "V1P8") (class "Default")
      (node (ref "1V8") (pin "1") (pinfunction "PT_1") (pintype "passive"))
      (node (ref "C12") (pin "1") (pinfunction "1_1") (pintype "passive"))
      (node (ref "U8") (pin "1") (pinfunction "OUT_1") (pintype "passive"))
    )
    (net (code "34") (name "V2P8") (class "Default")
      (node (ref "2V8") (pin "1") (pinfunction "PT_1") (pintype "passive"))
      (node (ref "C49") (pin "1") (pinfunction "1_1") (pintype "passive"))
      (node (ref "U9") (pin "1") (pinfunction "OUT_1") (pintype "passive"))
    )
    (net (code "35") (name "V3P0") (class "Default")
      (node (ref "C11") (pin "1") (pinfunction "1_1") (pintype "passive"))
      (node (ref "C23") (pin "1") (pinfunction "1_1") (pintype "passive"))
      (node (ref "C24") (pin "1") (pinfunction "1_1") (pintype "passive"))
      (node (ref "C25") (pin "1") (pinfunction "1_1") (pintype "passive"))
      (node (ref "C28") (pin "2") (pinfunction "2_2") (pintype "passive"))
      (node (ref "C48") (pin "1") (pinfunction "1_1") (pintype "passive"))
      (node (ref "C7") (pin "1") (pinfunction "1_1") (pintype "passive"))
      (node (ref "L1") (pin "2") (pinfunction "2_2") (pintype "passive"))
      (node (ref "R13") (pin "1") (pinfunction "1_1") (pintype "passive"))
      (node (ref "R16") (pin "1") (pinfunction "1_1") (pintype "passive"))
      (node (ref "U3") (pin "4") (pinfunction "IN_4") (pintype "passive"))
      (node (ref "U8") (pin "4") (pinfunction "IN_4") (pintype "passive"))
      (node (ref "U9") (pin "4") (pinfunction "IN_4") (pintype "passive"))
      (node (ref "V3P0") (pin "1") (pinfunction "PT_1") (pintype "passive"))
    )
    (net (code "36") (name "VSYS") (class "Default")
      (node (ref "C5") (pin "1") (pinfunction "1_1") (pintype "passive"))
      (node (ref "C6") (pin "1") (pinfunction "1_1") (pintype "passive"))
      (node (ref "C9") (pin "1") (pinfunction "1_1") (pintype "passive"))
      (node (ref "Q4") (pin "2") (pinfunction "S_2") (pintype "passive"))
      (node (ref "R26") (pin "2") (pinfunction "2_2") (pintype "passive"))
      (node (ref "R27") (pin "2") (pinfunction "2_2") (pintype "passive"))
      (node (ref "R5") (pin "1") (pinfunction "1_1") (pintype "passive"))
      (node (ref "U1") (pin "13") (pinfunction "SYS_13") (pintype "passive"))
      (node (ref "U1") (pin "14") (pinfunction "SYS_14") (pintype "passive"))
      (node (ref "U2") (pin "1") (pinfunction "VIN_1") (pintype "passive"))
      (node (ref "VSYS") (pin "1") (pinfunction "PT_1") (pintype "passive"))
    )
    (net (code "37") (name "VSYS_SWITCHED") (class "Default")
      (node (ref "C13") (pin "1") (pinfunction "1_1") (pintype "passive"))
      (node (ref "C19") (pin "1") (pinfunction "1_1") (pintype "passive"))
      (node (ref "C21") (pin "1") (pinfunction "1_1") (pintype "passive"))
      (node (ref "IC2") (pin "4") (pinfunction "VIN_4") (pintype "passive"))
      (node (ref "R9") (pin "1") (pinfunction "1_1") (pintype "passive"))
      (node (ref "U2") (pin "8") (pinfunction "VOUT_8") (pintype "passive"))
      (node (ref "VSW") (pin "1") (pinfunction "PT_1") (pintype "passive"))
    )
    (net (code "38") (name "VUSB") (class "Default")
      (node (ref "C1") (pin "1") (pinfunction "1_1") (pintype "passive"))
      (node (ref "C2") (pin "1") (pinfunction "1_1") (pintype "passive"))
      (node (ref "C26") (pin "1") (pinfunction "1_1") (pintype "passive"))
      (node (ref "C27") (pin "1") (pinfunction "1_1") (pintype "passive"))
      (node (ref "D1") (pin "5") (pinfunction "VCC_5") (pintype "passive"))
      (node (ref "F1") (pin "2") (pinfunction "2_2") (pintype "passive"))
      (node (ref "R6") (pin "2") (pinfunction "2_2") (pintype "passive"))
      (node (ref "R8") (pin "2") (pinfunction "2_2") (pintype "passive"))
      (node (ref "U1") (pin "11") (pinfunction "IN_11") (pintype "passive"))
      (node (ref "U1") (pin "12") (pinfunction "IN_12") (pintype "passive"))
    )
    (net (code "39") (name "unconnected-(J8-SBU1-PadA8)") (class "Default")
      (node (ref "J8") (pin "A8") (pinfunction "SBU1_A8") (pintype "passive"))
    )
    (net (code "40") (name "unconnected-(J8-SBU2-PadB8)") (class "Default")
      (node (ref "J8") (pin "B8") (pinfunction "SBU2_B8") (pintype "passive"))
    )
    (net (code "41") (name "unconnected-(U1-~{STAT1}-Pad10)") (class "Default")
      (node (ref "U1") (pin "10") (pinfunction "~{STAT1}_10") (pintype "passive"))
    )
    (net (code "42") (name "unconnected-(U2-NC-Pad2)") (class "Default")
      (node (ref "U2") (pin "2") (pinfunction "NC_2") (pintype "passive"))
    )
  )
)
